# pcb-breakout-ltc3625-tps63031.net
KiCad netlist of a schematic drawn in EAGLE
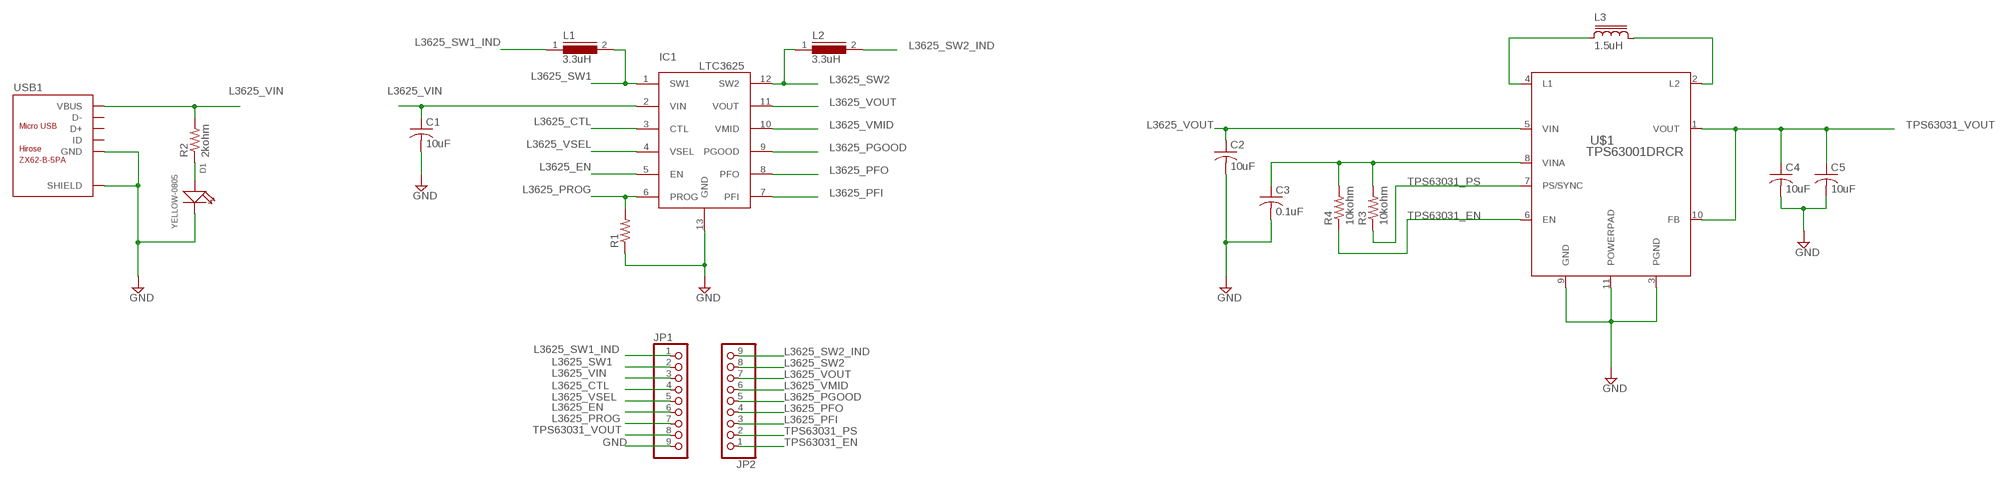
[diagram p0: schematic, sheet 1]

(export (version "E")
  (design (tool "Eeschema 10.0.6"))
  (components
    (comp (ref "C1")
      (value "10uF")
      (footprint "eagle-import:C0805")
      (libsource (lib "eagle-import") (part "C-USC0805"))
    )
    (comp (ref "C2")
      (value "10uF")
      (footprint "eagle-import:C0805")
      (libsource (lib "eagle-import") (part "C-USC0805"))
    )
    (comp (ref "C3")
      (value "0.1uF")
      (footprint "eagle-import:C0805")
      (libsource (lib "eagle-import") (part "C-USC0805"))
    )
    (comp (ref "C4")
      (value "10uF")
      (footprint "eagle-import:C0805")
      (libsource (lib "eagle-import") (part "C-USC0805"))
    )
    (comp (ref "C5")
      (value "10uF")
      (footprint "eagle-import:C0805")
      (libsource (lib "eagle-import") (part "C-USC0805"))
    )
    (comp (ref "D1")
      (value "YELLOW-0805")
      (footprint "eagle-import:LED-0805")
      (fields (field (name "MPN") "17-215UYC/S530-A3/TR8"))
      (libsource (lib "eagle-import") (part "SMD-LED-CLEAR-YELLOW(0805)"))
    )
    (comp (ref "IC1")
      (value "LTC3625EDE")
      (footprint "eagle-import:DFN12(DE)")
      (libsource (lib "eagle-import") (part "LTC3625EDE"))
    )
    (comp (ref "JP1")
      (value "PINHD-1X9")
      (footprint "eagle-import:1X09")
      (libsource (lib "eagle-import") (part "PINHD-1X9"))
    )
    (comp (ref "JP2")
      (value "PINHD-1X9")
      (footprint "eagle-import:1X09")
      (libsource (lib "eagle-import") (part "PINHD-1X9"))
    )
    (comp (ref "L1")
      (value "3.3uH")
      (footprint "eagle-import:DR73")
      (libsource (lib "eagle-import") (part "DR73"))
    )
    (comp (ref "L2")
      (value "3.3uH")
      (footprint "eagle-import:DR73")
      (libsource (lib "eagle-import") (part "DR73"))
    )
    (comp (ref "L3")
      (value "1.5uH")
      (footprint "eagle-import:LPS3015")
      (libsource (lib "eagle-import") (part "LPS3015"))
    )
    (comp (ref "R1")
      (value "R-US_R0805")
      (footprint "eagle-import:R0805")
      (libsource (lib "eagle-import") (part "R-US_R0805"))
    )
    (comp (ref "R2")
      (value "2kohm")
      (footprint "eagle-import:R0805")
      (libsource (lib "eagle-import") (part "R-US_R0805"))
    )
    (comp (ref "R3")
      (value "10kohm")
      (footprint "eagle-import:R0805")
      (libsource (lib "eagle-import") (part "R-US_R0805"))
    )
    (comp (ref "R4")
      (value "10kohm")
      (footprint "eagle-import:R0805")
      (libsource (lib "eagle-import") (part "R-US_R0805"))
    )
    (comp (ref "U$1")
      (value "TPS63001DRCR")
      (footprint "eagle-import:NEWPVSON-N10")
      (libsource (lib "eagle-import") (part "TPS63001DRCR"))
    )
    (comp (ref "USB1")
      (value "ZX62-B-5PA")
      (footprint "eagle-import:MICRO-USB5+6P-SMD-0.65-AB")
      (libsource (lib "eagle-import") (part "MICRO-USB-SMD(ZX62-B-5PA)"))
    )
  )
  (nets
    (net (code "1") (name "/L3625_CTL") (class "Default")
      (node (ref "IC1") (pin "3") (pinfunction "CTL_3") (pintype "bidirectional"))
      (node (ref "JP1") (pin "4") (pinfunction "4_4") (pintype "passive"))
    )
    (net (code "2") (name "/L3625_EN") (class "Default")
      (node (ref "IC1") (pin "5") (pinfunction "EN_5") (pintype "bidirectional"))
      (node (ref "JP1") (pin "6") (pinfunction "6_6") (pintype "passive"))
    )
    (net (code "3") (name "/L3625_PFI") (class "Default")
      (node (ref "IC1") (pin "7") (pinfunction "PFI_7") (pintype "bidirectional"))
      (node (ref "JP2") (pin "3") (pinfunction "3_3") (pintype "passive"))
    )
    (net (code "4") (name "/L3625_PFO") (class "Default")
      (node (ref "IC1") (pin "8") (pinfunction "PFO_8") (pintype "bidirectional"))
      (node (ref "JP2") (pin "4") (pinfunction "4_4") (pintype "passive"))
    )
    (net (code "5") (name "/L3625_PGOOD") (class "Default")
      (node (ref "IC1") (pin "9") (pinfunction "PGOOD_9") (pintype "bidirectional"))
      (node (ref "JP2") (pin "5") (pinfunction "5_5") (pintype "passive"))
    )
    (net (code "6") (name "/L3625_PROG") (class "Default")
      (node (ref "IC1") (pin "6") (pinfunction "PROG_6") (pintype "bidirectional"))
      (node (ref "JP1") (pin "7") (pinfunction "7_7") (pintype "passive"))
      (node (ref "R1") (pin "2") (pinfunction "2_2") (pintype "passive"))
    )
    (net (code "7") (name "/L3625_SW1") (class "Default")
      (node (ref "IC1") (pin "1") (pinfunction "SW1_1") (pintype "bidirectional"))
      (node (ref "JP1") (pin "2") (pinfunction "2_2") (pintype "passive"))
      (node (ref "L1") (pin "2") (pinfunction "2_2") (pintype "passive"))
    )
    (net (code "8") (name "/L3625_SW1_IND") (class "Default")
      (node (ref "JP1") (pin "1") (pinfunction "1_1") (pintype "passive"))
      (node (ref "L1") (pin "1") (pinfunction "1_1") (pintype "passive"))
    )
    (net (code "9") (name "/L3625_SW2") (class "Default")
      (node (ref "IC1") (pin "12") (pinfunction "SW2_12") (pintype "bidirectional"))
      (node (ref "JP2") (pin "8") (pinfunction "8_8") (pintype "passive"))
      (node (ref "L2") (pin "1") (pinfunction "1_1") (pintype "passive"))
    )
    (net (code "10") (name "/L3625_SW2_IND") (class "Default")
      (node (ref "JP2") (pin "9") (pinfunction "9_9") (pintype "passive"))
      (node (ref "L2") (pin "2") (pinfunction "2_2") (pintype "passive"))
    )
    (net (code "11") (name "/L3625_VIN") (class "Default")
      (node (ref "C1") (pin "1") (pinfunction "1_1") (pintype "passive"))
      (node (ref "IC1") (pin "2") (pinfunction "VIN_2") (pintype "bidirectional"))
      (node (ref "JP1") (pin "3") (pinfunction "3_3") (pintype "passive"))
      (node (ref "R2") (pin "2") (pinfunction "2_2") (pintype "passive"))
      (node (ref "USB1") (pin "1") (pinfunction "VBUS_1") (pintype "power_in"))
    )
    (net (code "12") (name "/L3625_VMID") (class "Default")
      (node (ref "IC1") (pin "10") (pinfunction "VMID_10") (pintype "bidirectional"))
      (node (ref "JP2") (pin "6") (pinfunction "6_6") (pintype "passive"))
    )
    (net (code "13") (name "/L3625_VOUT") (class "Default")
      (node (ref "C2") (pin "1") (pinfunction "1_1") (pintype "passive"))
      (node (ref "IC1") (pin "11") (pinfunction "VOUT_11") (pintype "bidirectional"))
      (node (ref "JP2") (pin "7") (pinfunction "7_7") (pintype "passive"))
      (node (ref "U$1") (pin "5") (pinfunction "VIN_5") (pintype "passive"))
    )
    (net (code "14") (name "/L3625_VSEL") (class "Default")
      (node (ref "IC1") (pin "4") (pinfunction "VSEL_4") (pintype "bidirectional"))
      (node (ref "JP1") (pin "5") (pinfunction "5_5") (pintype "passive"))
    )
    (net (code "15") (name "/TPS63031_EN") (class "Default")
      (node (ref "JP2") (pin "1") (pinfunction "1_1") (pintype "passive"))
      (node (ref "R4") (pin "1") (pinfunction "1_1") (pintype "passive"))
      (node (ref "U$1") (pin "6") (pinfunction "EN_6") (pintype "passive"))
    )
    (net (code "16") (name "/TPS63031_PS") (class "Default")
      (node (ref "JP2") (pin "2") (pinfunction "2_2") (pintype "passive"))
      (node (ref "R3") (pin "1") (pinfunction "1_1") (pintype "passive"))
      (node (ref "U$1") (pin "7") (pinfunction "PS/SYNC_7") (pintype "passive"))
    )
    (net (code "17") (name "/TPS63031_VOUT") (class "Default")
      (node (ref "C4") (pin "1") (pinfunction "1_1") (pintype "passive"))
      (node (ref "C5") (pin "1") (pinfunction "1_1") (pintype "passive"))
      (node (ref "JP1") (pin "8") (pinfunction "8_8") (pintype "passive"))
      (node (ref "U$1") (pin "1") (pinfunction "VOUT_1") (pintype "passive"))
      (node (ref "U$1") (pin "10") (pinfunction "FB_10") (pintype "passive"))
    )
    (net (code "18") (name "GND") (class "Default")
      (node (ref "C1") (pin "2") (pinfunction "2_2") (pintype "passive"))
      (node (ref "C2") (pin "2") (pinfunction "2_2") (pintype "passive"))
      (node (ref "C3") (pin "2") (pinfunction "2_2") (pintype "passive"))
      (node (ref "C4") (pin "2") (pinfunction "2_2") (pintype "passive"))
      (node (ref "C5") (pin "2") (pinfunction "2_2") (pintype "passive"))
      (node (ref "D1") (pin "-") (pinfunction "-_-") (pintype "passive"))
      (node (ref "IC1") (pin "13") (pinfunction "GND_13") (pintype "bidirectional"))
      (node (ref "JP1") (pin "9") (pinfunction "9_9") (pintype "passive"))
      (node (ref "R1") (pin "1") (pinfunction "1_1") (pintype "passive"))
      (node (ref "U$1") (pin "11") (pinfunction "POWERPAD_11") (pintype "passive"))
      (node (ref "U$1") (pin "3") (pinfunction "PGND_3") (pintype "passive"))
      (node (ref "U$1") (pin "9") (pinfunction "GND_9") (pintype "passive"))
      (node (ref "USB1") (pin "5") (pinfunction "GND_5") (pintype "power_in"))
      (node (ref "USB1") (pin "P1") (pinfunction "SHIELD_P1") (pintype "power_in"))
      (node (ref "USB1") (pin "P2") (pinfunction "SHIELD_P2") (pintype "power_in"))
      (node (ref "USB1") (pin "P3") (pinfunction "SHIELD_P3") (pintype "power_in"))
      (node (ref "USB1") (pin "P4") (pinfunction "SHIELD_P4") (pintype "power_in"))
      (node (ref "USB1") (pin "P5") (pinfunction "SHIELD_P5") (pintype "power_in"))
      (node (ref "USB1") (pin "P6") (pinfunction "SHIELD_P6") (pintype "power_in"))
    )
    (net (code "19") (name "Net-(D1-Pad+)") (class "Default")
      (node (ref "D1") (pin "+") (pinfunction "+_+") (pintype "passive"))
      (node (ref "R2") (pin "1") (pinfunction "1_1") (pintype "passive"))
    )
    (net (code "20") (name "Net-(U$1-L1)") (class "Default")
      (node (ref "L3") (pin "1") (pinfunction "1_1") (pintype "passive"))
      (node (ref "U$1") (pin "4") (pinfunction "L1_4") (pintype "passive"))
    )
    (net (code "21") (name "Net-(U$1-L2)") (class "Default")
      (node (ref "L3") (pin "2") (pinfunction "2_2") (pintype "passive"))
      (node (ref "U$1") (pin "2") (pinfunction "L2_2") (pintype "passive"))
    )
    (net (code "22") (name "Net-(U$1-VINA)") (class "Default")
      (node (ref "C3") (pin "1") (pinfunction "1_1") (pintype "passive"))
      (node (ref "R3") (pin "2") (pinfunction "2_2") (pintype "passive"))
      (node (ref "R4") (pin "2") (pinfunction "2_2") (pintype "passive"))
      (node (ref "U$1") (pin "8") (pinfunction "VINA_8") (pintype "passive"))
    )
    (net (code "23") (name "unconnected-(USB1-D+-Pad3)") (class "Default")
      (node (ref "USB1") (pin "3") (pinfunction "D+_3") (pintype "bidirectional"))
    )
    (net (code "24") (name "unconnected-(USB1-D--Pad2)") (class "Default")
      (node (ref "USB1") (pin "2") (pinfunction "D-_2") (pintype "bidirectional"))
    )
    (net (code "25") (name "unconnected-(USB1-ID-Pad4)") (class "Default")
      (node (ref "USB1") (pin "4") (pinfunction "ID_4") (pintype "bidirectional"))
    )
  )
)
